# KEY_Pad.net
KiCad netlist of a schematic drawn in Altium Designer
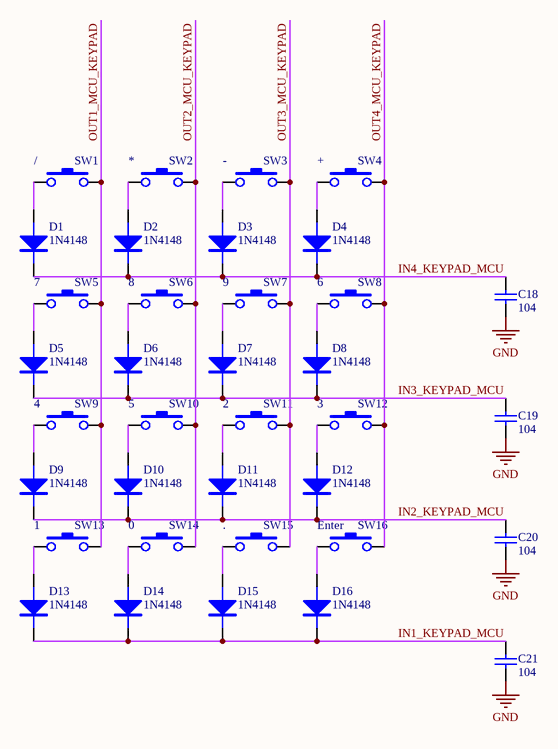
[diagram p0: KEY_Pad.SchDoc]

(export (version "E")
  (design (tool "Eeschema 10.0.6"))
  (components
    (comp (ref "C18")
      (value "104")
      (footprint "Cap-0603")
      (description "贴片陶瓷电容")
      (libsource (lib "Miscellaneous Base") (part "CAP"))
    )
    (comp (ref "C19")
      (value "104")
      (footprint "Cap-0603")
      (description "贴片陶瓷电容")
      (libsource (lib "Miscellaneous Base") (part "CAP"))
    )
    (comp (ref "C20")
      (value "104")
      (footprint "Cap-0603")
      (description "贴片陶瓷电容")
      (libsource (lib "Miscellaneous Base") (part "CAP"))
    )
    (comp (ref "C21")
      (value "104")
      (footprint "Cap-0603")
      (description "贴片陶瓷电容")
      (libsource (lib "Miscellaneous Base") (part "CAP"))
    )
    (comp (ref "D1")
      (value "1N4148")
      (footprint "SOD-523")
      (description "普通二极管")
      (libsource (lib "Miscellaneous Transistor") (part "DIODE"))
    )
    (comp (ref "D2")
      (value "1N4148")
      (footprint "SOD-523")
      (description "普通二极管")
      (libsource (lib "Miscellaneous Transistor") (part "DIODE"))
    )
    (comp (ref "D3")
      (value "1N4148")
      (footprint "SOD-523")
      (description "普通二极管")
      (libsource (lib "Miscellaneous Transistor") (part "DIODE"))
    )
    (comp (ref "D4")
      (value "1N4148")
      (footprint "SOD-523")
      (description "普通二极管")
      (libsource (lib "Miscellaneous Transistor") (part "DIODE"))
    )
    (comp (ref "D5")
      (value "1N4148")
      (footprint "SOD-523")
      (description "普通二极管")
      (libsource (lib "Miscellaneous Transistor") (part "DIODE"))
    )
    (comp (ref "D6")
      (value "1N4148")
      (footprint "SOD-523")
      (description "普通二极管")
      (libsource (lib "Miscellaneous Transistor") (part "DIODE"))
    )
    (comp (ref "D7")
      (value "1N4148")
      (footprint "SOD-523")
      (description "普通二极管")
      (libsource (lib "Miscellaneous Transistor") (part "DIODE"))
    )
    (comp (ref "D8")
      (value "1N4148")
      (footprint "SOD-523")
      (description "普通二极管")
      (libsource (lib "Miscellaneous Transistor") (part "DIODE"))
    )
    (comp (ref "D9")
      (value "1N4148")
      (footprint "SOD-523")
      (description "普通二极管")
      (libsource (lib "Miscellaneous Transistor") (part "DIODE"))
    )
    (comp (ref "D10")
      (value "1N4148")
      (footprint "SOD-523")
      (description "普通二极管")
      (libsource (lib "Miscellaneous Transistor") (part "DIODE"))
    )
    (comp (ref "D11")
      (value "1N4148")
      (footprint "SOD-523")
      (description "普通二极管")
      (libsource (lib "Miscellaneous Transistor") (part "DIODE"))
    )
    (comp (ref "D12")
      (value "1N4148")
      (footprint "SOD-523")
      (description "普通二极管")
      (libsource (lib "Miscellaneous Transistor") (part "DIODE"))
    )
    (comp (ref "D13")
      (value "1N4148")
      (footprint "SOD-523")
      (description "普通二极管")
      (libsource (lib "Miscellaneous Transistor") (part "DIODE"))
    )
    (comp (ref "D14")
      (value "1N4148")
      (footprint "SOD-523")
      (description "普通二极管")
      (libsource (lib "Miscellaneous Transistor") (part "DIODE"))
    )
    (comp (ref "D15")
      (value "1N4148")
      (footprint "SOD-523")
      (description "普通二极管")
      (libsource (lib "Miscellaneous Transistor") (part "DIODE"))
    )
    (comp (ref "D16")
      (value "1N4148")
      (footprint "SOD-523")
      (description "普通二极管")
      (libsource (lib "Miscellaneous Transistor") (part "DIODE"))
    )
    (comp (ref "SW1")
      (value "/")
      (footprint "MX_SW-4")
      (description "with Fixation pins  1-Pole")
      (libsource (lib "KeyBoard_rebacha") (part "MX_SW-4"))
    )
    (comp (ref "SW2")
      (value "*")
      (footprint "MX_SW-4")
      (description "with Fixation pins  1-Pole")
      (libsource (lib "KeyBoard_rebacha") (part "MX_SW-4"))
    )
    (comp (ref "SW3")
      (value "-")
      (footprint "MX_SW-4")
      (description "with Fixation pins  1-Pole")
      (libsource (lib "KeyBoard_rebacha") (part "MX_SW-4"))
    )
    (comp (ref "SW4")
      (value "+")
      (footprint "MX_SW-4")
      (description "with Fixation pins  1-Pole")
      (libsource (lib "KeyBoard_rebacha") (part "MX_SW-4"))
    )
    (comp (ref "SW5")
      (value "7")
      (footprint "MX_SW-4")
      (description "with Fixation pins  1-Pole")
      (libsource (lib "KeyBoard_rebacha") (part "MX_SW-4"))
    )
    (comp (ref "SW6")
      (value "8")
      (footprint "MX_SW-4")
      (description "with Fixation pins  1-Pole")
      (libsource (lib "KeyBoard_rebacha") (part "MX_SW-4"))
    )
    (comp (ref "SW7")
      (value "9")
      (footprint "MX_SW-4")
      (description "with Fixation pins  1-Pole")
      (libsource (lib "KeyBoard_rebacha") (part "MX_SW-4"))
    )
    (comp (ref "SW8")
      (value "6")
      (footprint "MX_SW-4")
      (description "with Fixation pins  1-Pole")
      (libsource (lib "KeyBoard_rebacha") (part "MX_SW-4"))
    )
    (comp (ref "SW9")
      (value "4")
      (footprint "MX_SW-4")
      (description "with Fixation pins  1-Pole")
      (libsource (lib "KeyBoard_rebacha") (part "MX_SW-4"))
    )
    (comp (ref "SW10")
      (value "5")
      (footprint "MX_SW-4")
      (description "with Fixation pins  1-Pole")
      (libsource (lib "KeyBoard_rebacha") (part "MX_SW-4"))
    )
    (comp (ref "SW11")
      (value "2")
      (footprint "MX_SW-4")
      (description "with Fixation pins  1-Pole")
      (libsource (lib "KeyBoard_rebacha") (part "MX_SW-4"))
    )
    (comp (ref "SW12")
      (value "3")
      (footprint "MX_SW-4")
      (description "with Fixation pins  1-Pole")
      (libsource (lib "KeyBoard_rebacha") (part "MX_SW-4"))
    )
    (comp (ref "SW13")
      (value "1")
      (footprint "MX_SW-4")
      (description "with Fixation pins  1-Pole")
      (libsource (lib "KeyBoard_rebacha") (part "MX_SW-4"))
    )
    (comp (ref "SW14")
      (value "0")
      (footprint "MX_SW-4")
      (description "with Fixation pins  1-Pole")
      (libsource (lib "KeyBoard_rebacha") (part "MX_SW-4"))
    )
    (comp (ref "SW15")
      (value ".")
      (footprint "MX_SW-4")
      (description "with Fixation pins  1-Pole")
      (libsource (lib "KeyBoard_rebacha") (part "MX_SW-4"))
    )
    (comp (ref "SW16")
      (value "Enter")
      (footprint "MX_SW-4")
      (description "with Fixation pins  1-Pole")
      (libsource (lib "KeyBoard_rebacha") (part "MX_SW-4"))
    )
  )
  (nets
    (net (code "1") (name "/IN1_KEYPAD_MCU") (class "Default")
      (node (ref "C21") (pin "2") (pinfunction "2_2") (pintype "passive"))
      (node (ref "D13") (pin "K") (pinfunction "K_K") (pintype "passive"))
      (node (ref "D14") (pin "K") (pinfunction "K_K") (pintype "passive"))
      (node (ref "D15") (pin "K") (pinfunction "K_K") (pintype "passive"))
      (node (ref "D16") (pin "K") (pinfunction "K_K") (pintype "passive"))
    )
    (net (code "2") (name "/IN2_KEYPAD_MCU") (class "Default")
      (node (ref "C20") (pin "2") (pinfunction "2_2") (pintype "passive"))
      (node (ref "D10") (pin "K") (pinfunction "K_K") (pintype "passive"))
      (node (ref "D11") (pin "K") (pinfunction "K_K") (pintype "passive"))
      (node (ref "D12") (pin "K") (pinfunction "K_K") (pintype "passive"))
      (node (ref "D9") (pin "K") (pinfunction "K_K") (pintype "passive"))
    )
    (net (code "3") (name "/IN3_KEYPAD_MCU") (class "Default")
      (node (ref "C19") (pin "1") (pinfunction "1_1") (pintype "passive"))
      (node (ref "D5") (pin "K") (pinfunction "K_K") (pintype "passive"))
      (node (ref "D6") (pin "K") (pinfunction "K_K") (pintype "passive"))
      (node (ref "D7") (pin "K") (pinfunction "K_K") (pintype "passive"))
      (node (ref "D8") (pin "K") (pinfunction "K_K") (pintype "passive"))
    )
    (net (code "4") (name "/IN4_KEYPAD_MCU") (class "Default")
      (node (ref "C18") (pin "1") (pinfunction "1_1") (pintype "passive"))
      (node (ref "D1") (pin "K") (pinfunction "K_K") (pintype "passive"))
      (node (ref "D2") (pin "K") (pinfunction "K_K") (pintype "passive"))
      (node (ref "D3") (pin "K") (pinfunction "K_K") (pintype "passive"))
      (node (ref "D4") (pin "K") (pinfunction "K_K") (pintype "passive"))
    )
    (net (code "5") (name "/OUT1_MCU_KEYPAD") (class "Default")
      (node (ref "SW1") (pin "2") (pinfunction "2_2") (pintype "passive"))
      (node (ref "SW13") (pin "2") (pinfunction "2_2") (pintype "passive"))
      (node (ref "SW5") (pin "2") (pinfunction "2_2") (pintype "passive"))
      (node (ref "SW9") (pin "2") (pinfunction "2_2") (pintype "passive"))
    )
    (net (code "6") (name "/OUT2_MCU_KEYPAD") (class "Default")
      (node (ref "SW10") (pin "2") (pinfunction "2_2") (pintype "passive"))
      (node (ref "SW14") (pin "2") (pinfunction "2_2") (pintype "passive"))
      (node (ref "SW2") (pin "2") (pinfunction "2_2") (pintype "passive"))
      (node (ref "SW6") (pin "2") (pinfunction "2_2") (pintype "passive"))
    )
    (net (code "7") (name "/OUT3_MCU_KEYPAD") (class "Default")
      (node (ref "SW11") (pin "2") (pinfunction "2_2") (pintype "passive"))
      (node (ref "SW15") (pin "2") (pinfunction "2_2") (pintype "passive"))
      (node (ref "SW3") (pin "2") (pinfunction "2_2") (pintype "passive"))
      (node (ref "SW7") (pin "2") (pinfunction "2_2") (pintype "passive"))
    )
    (net (code "8") (name "/OUT4_MCU_KEYPAD") (class "Default")
      (node (ref "SW12") (pin "2") (pinfunction "2_2") (pintype "passive"))
      (node (ref "SW16") (pin "2") (pinfunction "2_2") (pintype "passive"))
      (node (ref "SW4") (pin "2") (pinfunction "2_2") (pintype "passive"))
      (node (ref "SW8") (pin "2") (pinfunction "2_2") (pintype "passive"))
    )
    (net (code "9") (name "GND") (class "Default")
      (node (ref "C18") (pin "2") (pinfunction "2_2") (pintype "passive"))
      (node (ref "C19") (pin "2") (pinfunction "2_2") (pintype "passive"))
      (node (ref "C20") (pin "1") (pinfunction "1_1") (pintype "passive"))
      (node (ref "C21") (pin "1") (pinfunction "1_1") (pintype "passive"))
    )
    (net (code "10") (name "Net-(D1-PadA)") (class "Default")
      (node (ref "D1") (pin "A") (pinfunction "A_A") (pintype "passive"))
      (node (ref "SW1") (pin "1") (pinfunction "1_1") (pintype "passive"))
    )
    (net (code "11") (name "Net-(D2-PadA)") (class "Default")
      (node (ref "D2") (pin "A") (pinfunction "A_A") (pintype "passive"))
      (node (ref "SW2") (pin "1") (pinfunction "1_1") (pintype "passive"))
    )
    (net (code "12") (name "Net-(D3-PadA)") (class "Default")
      (node (ref "D3") (pin "A") (pinfunction "A_A") (pintype "passive"))
      (node (ref "SW3") (pin "1") (pinfunction "1_1") (pintype "passive"))
    )
    (net (code "13") (name "Net-(D4-PadA)") (class "Default")
      (node (ref "D4") (pin "A") (pinfunction "A_A") (pintype "passive"))
      (node (ref "SW4") (pin "1") (pinfunction "1_1") (pintype "passive"))
    )
    (net (code "14") (name "Net-(D5-PadA)") (class "Default")
      (node (ref "D5") (pin "A") (pinfunction "A_A") (pintype "passive"))
      (node (ref "SW5") (pin "1") (pinfunction "1_1") (pintype "passive"))
    )
    (net (code "15") (name "Net-(D6-PadA)") (class "Default")
      (node (ref "D6") (pin "A") (pinfunction "A_A") (pintype "passive"))
      (node (ref "SW6") (pin "1") (pinfunction "1_1") (pintype "passive"))
    )
    (net (code "16") (name "Net-(D7-PadA)") (class "Default")
      (node (ref "D7") (pin "A") (pinfunction "A_A") (pintype "passive"))
      (node (ref "SW7") (pin "1") (pinfunction "1_1") (pintype "passive"))
    )
    (net (code "17") (name "Net-(D8-PadA)") (class "Default")
      (node (ref "D8") (pin "A") (pinfunction "A_A") (pintype "passive"))
      (node (ref "SW8") (pin "1") (pinfunction "1_1") (pintype "passive"))
    )
    (net (code "18") (name "Net-(D9-PadA)") (class "Default")
      (node (ref "D9") (pin "A") (pinfunction "A_A") (pintype "passive"))
      (node (ref "SW9") (pin "1") (pinfunction "1_1") (pintype "passive"))
    )
    (net (code "19") (name "Net-(D10-PadA)") (class "Default")
      (node (ref "D10") (pin "A") (pinfunction "A_A") (pintype "passive"))
      (node (ref "SW10") (pin "1") (pinfunction "1_1") (pintype "passive"))
    )
    (net (code "20") (name "Net-(D11-PadA)") (class "Default")
      (node (ref "D11") (pin "A") (pinfunction "A_A") (pintype "passive"))
      (node (ref "SW11") (pin "1") (pinfunction "1_1") (pintype "passive"))
    )
    (net (code "21") (name "Net-(D12-PadA)") (class "Default")
      (node (ref "D12") (pin "A") (pinfunction "A_A") (pintype "passive"))
      (node (ref "SW12") (pin "1") (pinfunction "1_1") (pintype "passive"))
    )
    (net (code "22") (name "Net-(D13-PadA)") (class "Default")
      (node (ref "D13") (pin "A") (pinfunction "A_A") (pintype "passive"))
      (node (ref "SW13") (pin "1") (pinfunction "1_1") (pintype "passive"))
    )
    (net (code "23") (name "Net-(D14-PadA)") (class "Default")
      (node (ref "D14") (pin "A") (pinfunction "A_A") (pintype "passive"))
      (node (ref "SW14") (pin "1") (pinfunction "1_1") (pintype "passive"))
    )
    (net (code "24") (name "Net-(D15-PadA)") (class "Default")
      (node (ref "D15") (pin "A") (pinfunction "A_A") (pintype "passive"))
      (node (ref "SW15") (pin "1") (pinfunction "1_1") (pintype "passive"))
    )
    (net (code "25") (name "Net-(D16-PadA)") (class "Default")
      (node (ref "D16") (pin "A") (pinfunction "A_A") (pintype "passive"))
      (node (ref "SW16") (pin "1") (pinfunction "1_1") (pintype "passive"))
    )
  )
)
